# Painel.net
KiCad netlist of a schematic drawn in EAGLE
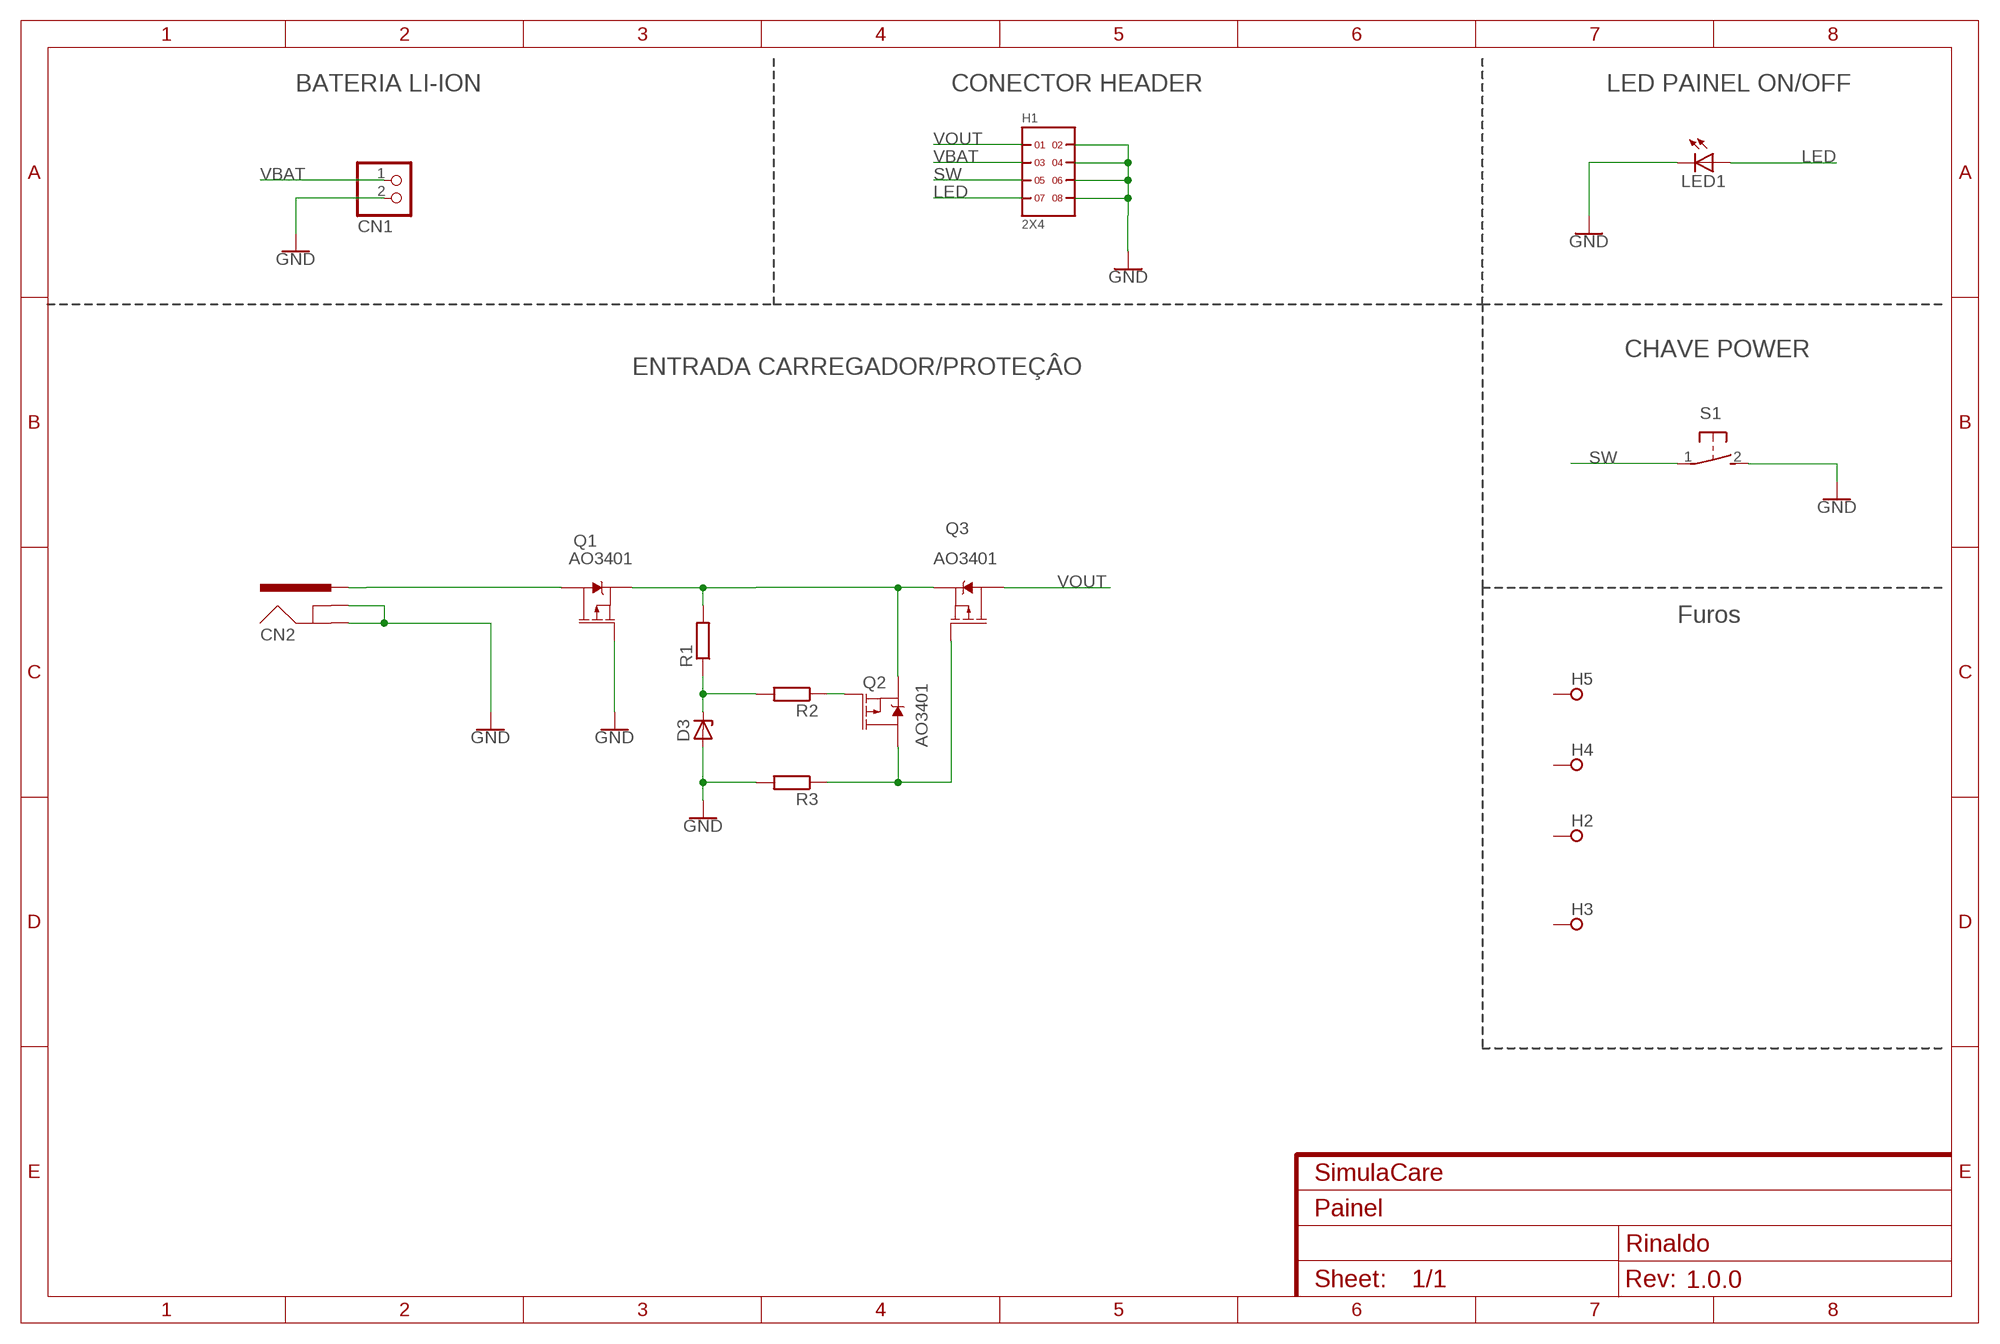
[diagram p0: schematic, sheet 1]

(export (version "E")
  (design (tool "Eeschema 10.0.6"))
  (components
    (comp (ref "CN1")
      (value "JST_2PIN-THM")
      (footprint "eagle-import:JST-PH-2-THM")
      (libsource (lib "eagle-import") (part "JST_2PIN-THM"))
    )
    (comp (ref "CN2")
      (value "POWERJACK")
      (footprint "eagle-import:POWERJACK")
      (libsource (lib "eagle-import") (part "POWERJACK"))
    )
    (comp (ref "D3")
      (value "ZENER-DIODESOT23")
      (footprint "eagle-import:SOT23")
      (libsource (lib "eagle-import") (part "ZENER-DIODESOT23"))
    )
    (comp (ref "H1")
      (value "2X4")
      (footprint "eagle-import:2X4")
      (libsource (lib "eagle-import") (part "2X4"))
    )
    (comp (ref "H2")
      (value "SPECIAL_DRILL_0.1250")
      (footprint "eagle-import:PAD_0.1250")
      (libsource (lib "eagle-import") (part "SPECIAL_DRILL_0.1250"))
    )
    (comp (ref "H3")
      (value "SPECIAL_DRILL_0.1250")
      (footprint "eagle-import:PAD_0.1250")
      (libsource (lib "eagle-import") (part "SPECIAL_DRILL_0.1250"))
    )
    (comp (ref "H4")
      (value "SPECIAL_DRILL_0.1250")
      (footprint "eagle-import:PAD_0.1250")
      (libsource (lib "eagle-import") (part "SPECIAL_DRILL_0.1250"))
    )
    (comp (ref "H5")
      (value "SPECIAL_DRILL_0.1250")
      (footprint "eagle-import:PAD_0.1250")
      (libsource (lib "eagle-import") (part "SPECIAL_DRILL_0.1250"))
    )
    (comp (ref "LED1")
      (value "LED3MM")
      (footprint "eagle-import:LED3MM")
      (libsource (lib "eagle-import") (part "LED3MM"))
    )
    (comp (ref "Q1")
      (value "AO3401")
      (footprint "eagle-import:SOT23-3")
      (libsource (lib "eagle-import") (part "MOSFET_PCH-IRLML2244"))
    )
    (comp (ref "Q2")
      (value "AO3401")
      (footprint "eagle-import:SOT23-3")
      (libsource (lib "eagle-import") (part "MOSFET_PCH-IRLML2244"))
    )
    (comp (ref "Q3")
      (value "AO3401")
      (footprint "eagle-import:SOT23-3")
      (libsource (lib "eagle-import") (part "MOSFET_PCH-IRLML2244"))
    )
    (comp (ref "R1")
      (value "R-EU_R0603")
      (footprint "eagle-import:R0603")
      (libsource (lib "eagle-import") (part "R-EU_R0603"))
    )
    (comp (ref "R2")
      (value "R-EU_R0603")
      (footprint "eagle-import:R0603")
      (libsource (lib "eagle-import") (part "R-EU_R0603"))
    )
    (comp (ref "R3")
      (value "R-EU_R0603")
      (footprint "eagle-import:R0603")
      (libsource (lib "eagle-import") (part "R-EU_R0603"))
    )
    (comp (ref "S1")
      (value "31-XX")
      (footprint "eagle-import:B3F-31XX")
      (libsource (lib "eagle-import") (part "31-XX"))
    )
  )
  (nets
    (net (code "1") (name "/LED") (class "Default")
      (node (ref "H1") (pin "7") (pinfunction "7_7") (pintype "bidirectional"))
      (node (ref "LED1") (pin "A") (pinfunction "A_A") (pintype "passive"))
    )
    (net (code "2") (name "/SW") (class "Default")
      (node (ref "H1") (pin "5") (pinfunction "5_5") (pintype "bidirectional"))
      (node (ref "S1") (pin "1") (pinfunction "P_1") (pintype "passive"))
    )
    (net (code "3") (name "/VBAT") (class "Default")
      (node (ref "CN1") (pin "1") (pinfunction "2_1") (pintype "passive"))
      (node (ref "H1") (pin "3") (pinfunction "3_3") (pintype "bidirectional"))
    )
    (net (code "4") (name "/VOUT") (class "Default")
      (node (ref "H1") (pin "1") (pinfunction "1_1") (pintype "bidirectional"))
      (node (ref "Q3") (pin "3") (pinfunction "D_3") (pintype "bidirectional"))
    )
    (net (code "5") (name "GND") (class "Default")
      (node (ref "CN1") (pin "2") (pinfunction "1_2") (pintype "passive"))
      (node (ref "CN2") (pin "GND") (pinfunction "GND_GND") (pintype "bidirectional"))
      (node (ref "CN2") (pin "GNDBREAK") (pinfunction "GNDBREAK_GNDBREAK") (pintype "bidirectional"))
      (node (ref "D3") (pin "1") (pinfunction "A_1") (pintype "passive"))
      (node (ref "H1") (pin "2") (pinfunction "2_2") (pintype "bidirectional"))
      (node (ref "H1") (pin "4") (pinfunction "4_4") (pintype "bidirectional"))
      (node (ref "H1") (pin "6") (pinfunction "6_6") (pintype "bidirectional"))
      (node (ref "H1") (pin "8") (pinfunction "8_8") (pintype "bidirectional"))
      (node (ref "LED1") (pin "K") (pinfunction "C_K") (pintype "passive"))
      (node (ref "Q1") (pin "1") (pinfunction "G_1") (pintype "bidirectional"))
      (node (ref "R3") (pin "2") (pinfunction "2_2") (pintype "passive"))
      (node (ref "S1") (pin "2") (pinfunction "S_2") (pintype "passive"))
    )
    (net (code "6") (name "Net-(D3-C)") (class "Default")
      (node (ref "D3") (pin "3") (pinfunction "C_3") (pintype "passive"))
      (node (ref "R1") (pin "1") (pinfunction "1_1") (pintype "passive"))
      (node (ref "R2") (pin "2") (pinfunction "2_2") (pintype "passive"))
    )
    (net (code "7") (name "Net-(Q1-D)") (class "Default")
      (node (ref "CN2") (pin "PWR") (pinfunction "PWR_PWR") (pintype "bidirectional"))
      (node (ref "Q1") (pin "3") (pinfunction "D_3") (pintype "bidirectional"))
    )
    (net (code "8") (name "Net-(Q1-S)") (class "Default")
      (node (ref "Q1") (pin "2") (pinfunction "S_2") (pintype "bidirectional"))
      (node (ref "Q2") (pin "2") (pinfunction "S_2") (pintype "bidirectional"))
      (node (ref "Q3") (pin "2") (pinfunction "S_2") (pintype "bidirectional"))
      (node (ref "R1") (pin "2") (pinfunction "2_2") (pintype "passive"))
    )
    (net (code "9") (name "Net-(Q2-D)") (class "Default")
      (node (ref "Q2") (pin "3") (pinfunction "D_3") (pintype "bidirectional"))
      (node (ref "Q3") (pin "1") (pinfunction "G_1") (pintype "bidirectional"))
      (node (ref "R3") (pin "1") (pinfunction "1_1") (pintype "passive"))
    )
    (net (code "10") (name "Net-(Q2-G)") (class "Default")
      (node (ref "Q2") (pin "1") (pinfunction "G_1") (pintype "bidirectional"))
      (node (ref "R2") (pin "1") (pinfunction "1_1") (pintype "passive"))
    )
    (net (code "11") (name "unconnected-(H2-Pad1)") (class "Default")
      (node (ref "H2") (pin "1") (pinfunction "1_1") (pintype "passive"))
    )
    (net (code "12") (name "unconnected-(H3-Pad1)") (class "Default")
      (node (ref "H3") (pin "1") (pinfunction "1_1") (pintype "passive"))
    )
    (net (code "13") (name "unconnected-(H4-Pad1)") (class "Default")
      (node (ref "H4") (pin "1") (pinfunction "1_1") (pintype "passive"))
    )
    (net (code "14") (name "unconnected-(H5-Pad1)") (class "Default")
      (node (ref "H5") (pin "1") (pinfunction "1_1") (pintype "passive"))
    )
  )
)
